# EL_Inverter.net
KiCad netlist of a schematic drawn in EAGLE
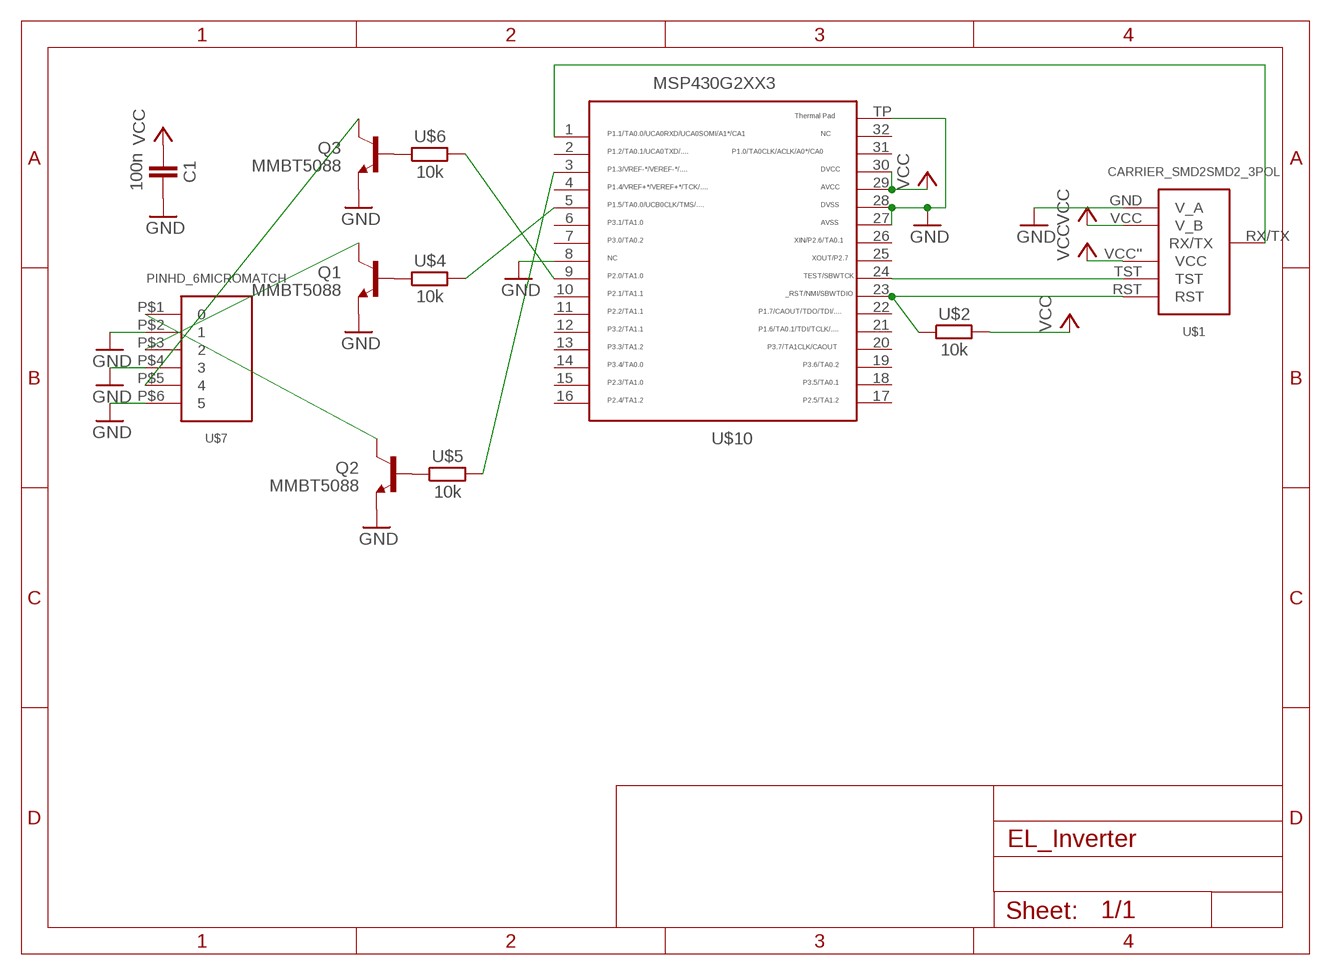
[diagram p0: schematic, sheet 1]

(export (version "E")
  (design (tool "Eeschema 10.0.6"))
  (components
    (comp (ref "C1")
      (value "100n")
      (footprint "eagle-import:603")
      (libsource (lib "eagle-import") (part "CAPACITOR"))
    )
    (comp (ref "Q1")
      (value "MMBT5088")
      (footprint "eagle-import:SOT23-3")
      (libsource (lib "eagle-import") (part "TRANSISTOR_NPNMMBT5088"))
    )
    (comp (ref "Q2")
      (value "MMBT5088")
      (footprint "eagle-import:SOT23-3")
      (libsource (lib "eagle-import") (part "TRANSISTOR_NPNMMBT5088"))
    )
    (comp (ref "Q3")
      (value "MMBT5088")
      (footprint "eagle-import:SOT23-3")
      (libsource (lib "eagle-import") (part "TRANSISTOR_NPNMMBT5088"))
    )
    (comp (ref "U$1")
      (value "CARRIER_SMD2SMD2_3POL")
      (footprint "eagle-import:CARRIER_SMD2_3POL")
      (libsource (lib "eagle-import") (part "CARRIER_SMD2SMD2_3POL"))
    )
    (comp (ref "U$2")
      (value "10k")
      (footprint "eagle-import:603")
      (libsource (lib "eagle-import") (part "RESISTOR0603"))
    )
    (comp (ref "U$4")
      (value "10k")
      (footprint "eagle-import:603")
      (libsource (lib "eagle-import") (part "RESISTOR0603"))
    )
    (comp (ref "U$5")
      (value "10k")
      (footprint "eagle-import:603")
      (libsource (lib "eagle-import") (part "RESISTOR0603"))
    )
    (comp (ref "U$6")
      (value "10k")
      (footprint "eagle-import:603")
      (libsource (lib "eagle-import") (part "RESISTOR0603"))
    )
    (comp (ref "U$7")
      (value "PINHD_6MICROMATCH")
      (footprint "eagle-import:MICROMATCH6POL")
      (libsource (lib "eagle-import") (part "PINHD_6MICROMATCH"))
    )
    (comp (ref "U$10")
      (value "MSP430G2553")
      (footprint "eagle-import:QFN32")
      (libsource (lib "eagle-import") (part "MSP430G2553"))
    )
  )
  (nets
    (net (code "1") (name "GND") (class "Default")
      (node (ref "C1") (pin "2") (pinfunction "2_2") (pintype "passive"))
      (node (ref "Q1") (pin "2") (pinfunction "E_2") (pintype "passive"))
      (node (ref "Q2") (pin "2") (pinfunction "E_2") (pintype "passive"))
      (node (ref "Q3") (pin "2") (pinfunction "E_2") (pintype "passive"))
      (node (ref "U$1") (pin "GND") (pinfunction "V_A_GND") (pintype "bidirectional"))
      (node (ref "U$10") (pin "27") (pinfunction "27_27") (pintype "bidirectional"))
      (node (ref "U$10") (pin "28") (pinfunction "28_28") (pintype "bidirectional"))
      (node (ref "U$10") (pin "8") (pinfunction "8_8") (pintype "bidirectional"))
      (node (ref "U$10") (pin "TP") (pinfunction "TP_TP") (pintype "bidirectional"))
      (node (ref "U$7") (pin "P$2") (pinfunction "1_P$2") (pintype "bidirectional"))
      (node (ref "U$7") (pin "P$4") (pinfunction "3_P$4") (pintype "bidirectional"))
      (node (ref "U$7") (pin "P$6") (pinfunction "5_P$6") (pintype "bidirectional"))
    )
    (net (code "2") (name "Net-(Q1-B)") (class "Default")
      (node (ref "Q1") (pin "1") (pinfunction "B_1") (pintype "passive"))
      (node (ref "U$4") (pin "1") (pinfunction "1_1") (pintype "passive"))
    )
    (net (code "3") (name "Net-(Q1-C)") (class "Default")
      (node (ref "Q1") (pin "3") (pinfunction "C_3") (pintype "passive"))
      (node (ref "U$7") (pin "P$3") (pinfunction "2_P$3") (pintype "bidirectional"))
    )
    (net (code "4") (name "Net-(Q2-B)") (class "Default")
      (node (ref "Q2") (pin "1") (pinfunction "B_1") (pintype "passive"))
      (node (ref "U$5") (pin "1") (pinfunction "1_1") (pintype "passive"))
    )
    (net (code "5") (name "Net-(Q2-C)") (class "Default")
      (node (ref "Q2") (pin "3") (pinfunction "C_3") (pintype "passive"))
      (node (ref "U$7") (pin "P$1") (pinfunction "0_P$1") (pintype "bidirectional"))
    )
    (net (code "6") (name "Net-(Q3-B)") (class "Default")
      (node (ref "Q3") (pin "1") (pinfunction "B_1") (pintype "passive"))
      (node (ref "U$6") (pin "1") (pinfunction "1_1") (pintype "passive"))
    )
    (net (code "7") (name "Net-(Q3-C)") (class "Default")
      (node (ref "Q3") (pin "3") (pinfunction "C_3") (pintype "passive"))
      (node (ref "U$7") (pin "P$5") (pinfunction "4_P$5") (pintype "bidirectional"))
    )
    (net (code "8") (name "Net-(U$1-PadRST)") (class "Default")
      (node (ref "U$1") (pin "RST") (pinfunction "RST_RST") (pintype "bidirectional"))
      (node (ref "U$10") (pin "23") (pinfunction "23_23") (pintype "bidirectional"))
      (node (ref "U$2") (pin "1") (pinfunction "1_1") (pintype "passive"))
    )
    (net (code "9") (name "Net-(U$1-PadRX{slash}TX)") (class "Default")
      (node (ref "U$1") (pin "RX/TX") (pinfunction "RX/TX_RX/TX") (pintype "bidirectional"))
      (node (ref "U$10") (pin "1") (pinfunction "1_1") (pintype "bidirectional"))
    )
    (net (code "10") (name "Net-(U$1-PadTST)") (class "Default")
      (node (ref "U$1") (pin "TST") (pinfunction "TST_TST") (pintype "bidirectional"))
      (node (ref "U$10") (pin "24") (pinfunction "24_24") (pintype "bidirectional"))
    )
    (net (code "11") (name "Net-(U$10-Pad3)") (class "Default")
      (node (ref "U$10") (pin "3") (pinfunction "3_3") (pintype "bidirectional"))
      (node (ref "U$5") (pin "2") (pinfunction "2_2") (pintype "passive"))
    )
    (net (code "12") (name "Net-(U$10-Pad5)") (class "Default")
      (node (ref "U$10") (pin "5") (pinfunction "5_5") (pintype "bidirectional"))
      (node (ref "U$4") (pin "2") (pinfunction "2_2") (pintype "passive"))
    )
    (net (code "13") (name "Net-(U$10-Pad9)") (class "Default")
      (node (ref "U$10") (pin "9") (pinfunction "9_9") (pintype "bidirectional"))
      (node (ref "U$6") (pin "2") (pinfunction "2_2") (pintype "passive"))
    )
    (net (code "14") (name "VCC") (class "Default")
      (node (ref "C1") (pin "1") (pinfunction "1_1") (pintype "passive"))
      (node (ref "U$1") (pin "VCC") (pinfunction "V_B_VCC") (pintype "bidirectional"))
      (node (ref "U$1") (pin "VCC''") (pinfunction "VCC_VCC''") (pintype "bidirectional"))
      (node (ref "U$10") (pin "29") (pinfunction "29_29") (pintype "bidirectional"))
      (node (ref "U$10") (pin "30") (pinfunction "30_30") (pintype "bidirectional"))
      (node (ref "U$2") (pin "2") (pinfunction "2_2") (pintype "passive"))
    )
    (net (code "15") (name "unconnected-(U$10-Pad2)") (class "Default")
      (node (ref "U$10") (pin "2") (pinfunction "2_2") (pintype "bidirectional"))
    )
    (net (code "16") (name "unconnected-(U$10-Pad4)") (class "Default")
      (node (ref "U$10") (pin "4") (pinfunction "4_4") (pintype "bidirectional"))
    )
    (net (code "17") (name "unconnected-(U$10-Pad6)") (class "Default")
      (node (ref "U$10") (pin "6") (pinfunction "6_6") (pintype "bidirectional"))
    )
    (net (code "18") (name "unconnected-(U$10-Pad7)") (class "Default")
      (node (ref "U$10") (pin "7") (pinfunction "7_7") (pintype "bidirectional"))
    )
    (net (code "19") (name "unconnected-(U$10-Pad10)") (class "Default")
      (node (ref "U$10") (pin "10") (pinfunction "10_10") (pintype "bidirectional"))
    )
    (net (code "20") (name "unconnected-(U$10-Pad11)") (class "Default")
      (node (ref "U$10") (pin "11") (pinfunction "11_11") (pintype "bidirectional"))
    )
    (net (code "21") (name "unconnected-(U$10-Pad12)") (class "Default")
      (node (ref "U$10") (pin "12") (pinfunction "12_12") (pintype "bidirectional"))
    )
    (net (code "22") (name "unconnected-(U$10-Pad13)") (class "Default")
      (node (ref "U$10") (pin "13") (pinfunction "13_13") (pintype "bidirectional"))
    )
    (net (code "23") (name "unconnected-(U$10-Pad14)") (class "Default")
      (node (ref "U$10") (pin "14") (pinfunction "14_14") (pintype "bidirectional"))
    )
    (net (code "24") (name "unconnected-(U$10-Pad15)") (class "Default")
      (node (ref "U$10") (pin "15") (pinfunction "15_15") (pintype "bidirectional"))
    )
    (net (code "25") (name "unconnected-(U$10-Pad16)") (class "Default")
      (node (ref "U$10") (pin "16") (pinfunction "16_16") (pintype "bidirectional"))
    )
    (net (code "26") (name "unconnected-(U$10-Pad17)") (class "Default")
      (node (ref "U$10") (pin "17") (pinfunction "17_17") (pintype "bidirectional"))
    )
    (net (code "27") (name "unconnected-(U$10-Pad18)") (class "Default")
      (node (ref "U$10") (pin "18") (pinfunction "18_18") (pintype "bidirectional"))
    )
    (net (code "28") (name "unconnected-(U$10-Pad19)") (class "Default")
      (node (ref "U$10") (pin "19") (pinfunction "19_19") (pintype "bidirectional"))
    )
    (net (code "29") (name "unconnected-(U$10-Pad20)") (class "Default")
      (node (ref "U$10") (pin "20") (pinfunction "20_20") (pintype "bidirectional"))
    )
    (net (code "30") (name "unconnected-(U$10-Pad21)") (class "Default")
      (node (ref "U$10") (pin "21") (pinfunction "21_21") (pintype "bidirectional"))
    )
    (net (code "31") (name "unconnected-(U$10-Pad22)") (class "Default")
      (node (ref "U$10") (pin "22") (pinfunction "22_22") (pintype "bidirectional"))
    )
    (net (code "32") (name "unconnected-(U$10-Pad25)") (class "Default")
      (node (ref "U$10") (pin "25") (pinfunction "25_25") (pintype "bidirectional"))
    )
    (net (code "33") (name "unconnected-(U$10-Pad26)") (class "Default")
      (node (ref "U$10") (pin "26") (pinfunction "26_26") (pintype "bidirectional"))
    )
    (net (code "34") (name "unconnected-(U$10-Pad31)") (class "Default")
      (node (ref "U$10") (pin "31") (pinfunction "31_31") (pintype "bidirectional"))
    )
    (net (code "35") (name "unconnected-(U$10-Pad32)") (class "Default")
      (node (ref "U$10") (pin "32") (pinfunction "32_32") (pintype "bidirectional"))
    )
  )
)
